# dual_pol_balun_multilayer.net
KiCad netlist of a schematic drawn in EAGLE
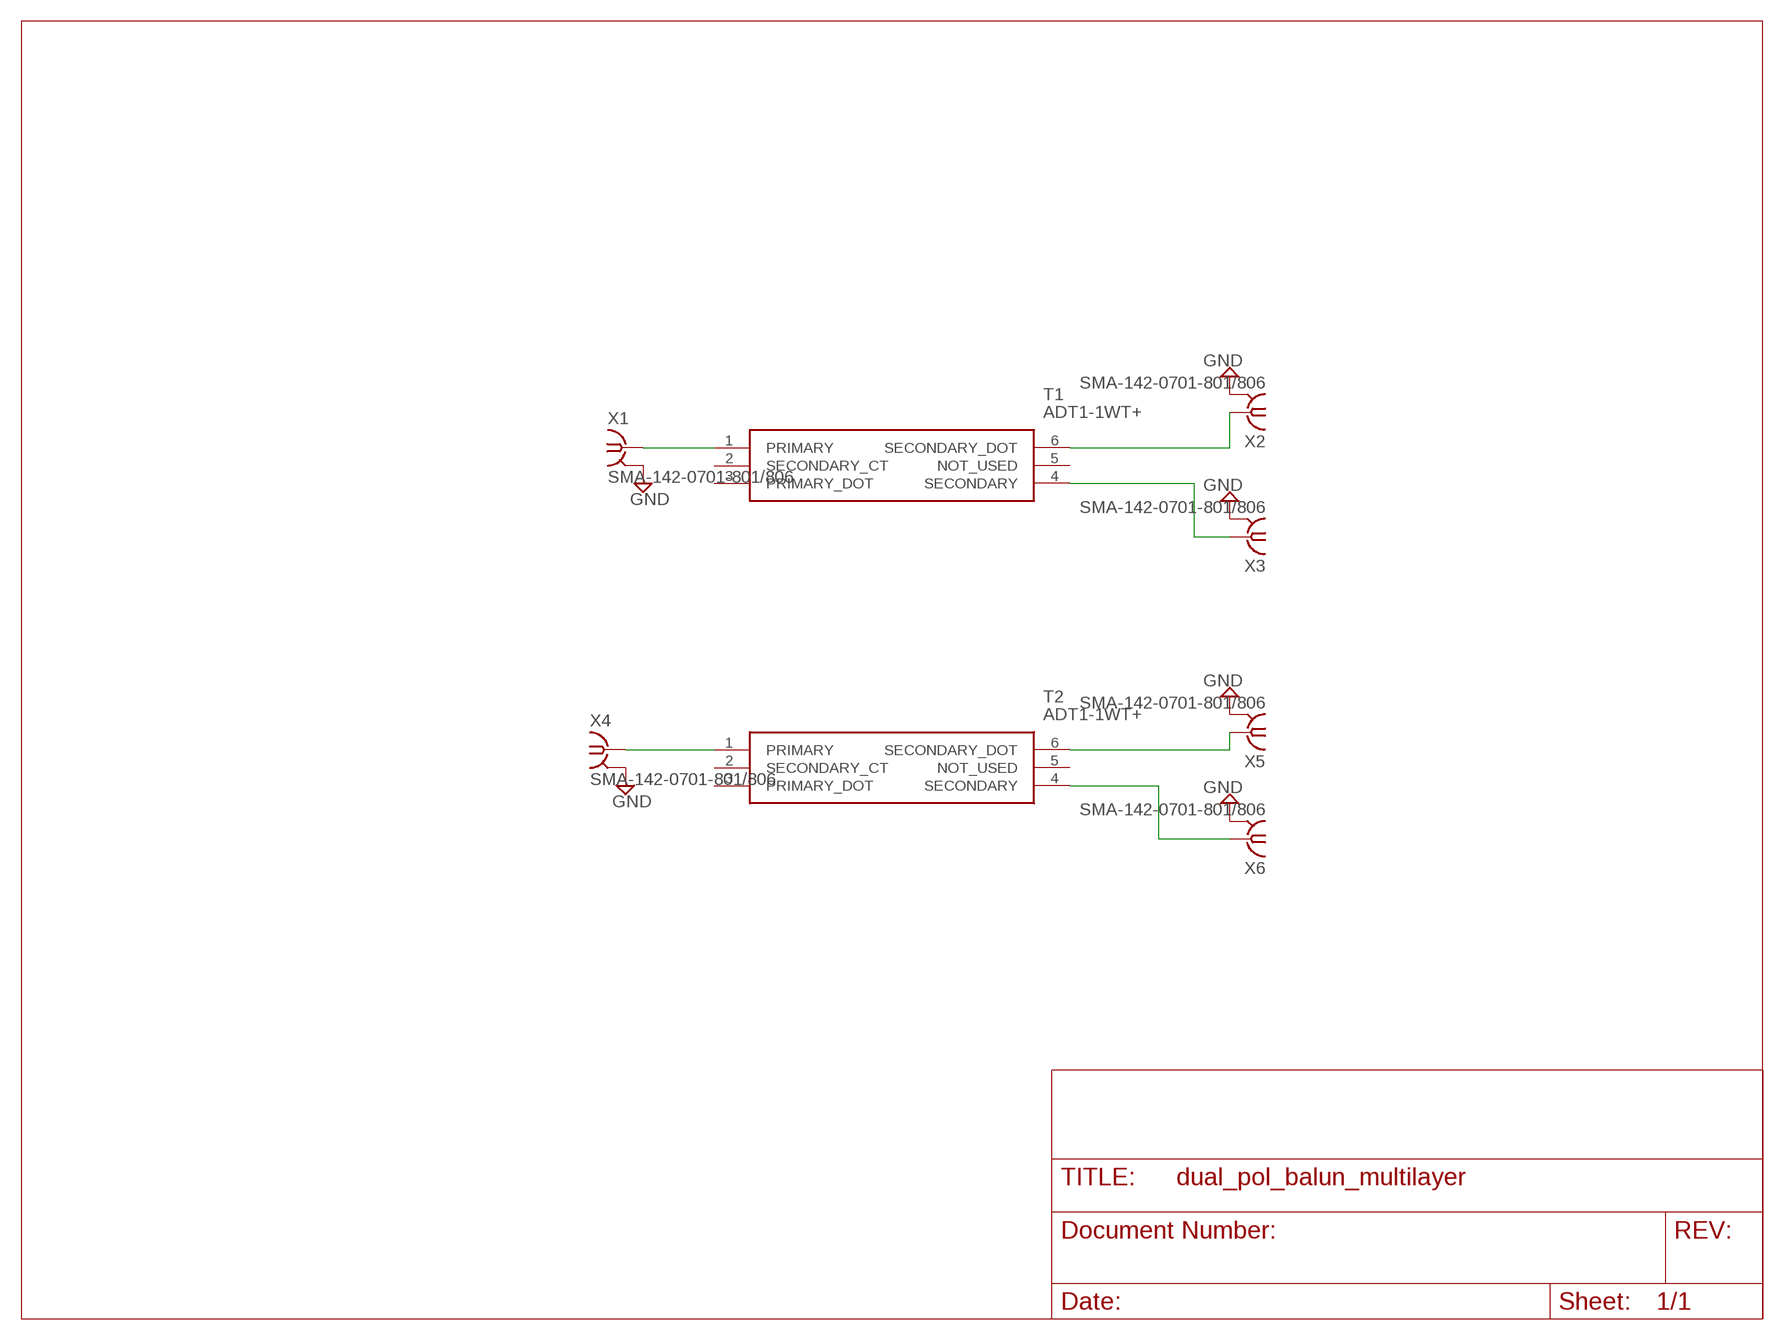
[diagram p0: schematic, sheet 1]

(export (version "E")
  (design (tool "Eeschema 10.0.6"))
  (components
    (comp (ref "T1")
      (value "ADT1-1WT+")
      (footprint "eagle-import:ADT11WT")
      (fields (field (name "MOUSER_PART_NUMBER") "139-ADT1-1WT"))
      (libsource (lib "eagle-import") (part "ADT1-1WT+"))
    )
    (comp (ref "T2")
      (value "ADT1-1WT+")
      (footprint "eagle-import:ADT11WT")
      (fields (field (name "MOUSER_PART_NUMBER") "139-ADT1-1WT"))
      (libsource (lib "eagle-import") (part "ADT1-1WT+"))
    )
    (comp (ref "X1")
      (value "SMA-142-0701-801/806")
      (footprint "eagle-import:J502-ND-142-0701-801_806")
      (fields (field (name "MF") "JOHNSON COMPONENTS") (field (name "MPN") "142-0701-801"))
      (libsource (lib "eagle-import") (part "SMA-142-0701-801/806"))
    )
    (comp (ref "X2")
      (value "SMA-142-0701-801/806")
      (footprint "eagle-import:J502-ND-142-0701-801_806")
      (fields (field (name "MF") "JOHNSON COMPONENTS") (field (name "MPN") "142-0701-801"))
      (libsource (lib "eagle-import") (part "SMA-142-0701-801/806"))
    )
    (comp (ref "X3")
      (value "SMA-142-0701-801/806")
      (footprint "eagle-import:J502-ND-142-0701-801_806")
      (fields (field (name "MF") "JOHNSON COMPONENTS") (field (name "MPN") "142-0701-801"))
      (libsource (lib "eagle-import") (part "SMA-142-0701-801/806"))
    )
    (comp (ref "X4")
      (value "SMA-142-0701-801/806")
      (footprint "eagle-import:J502-ND-142-0701-801_806")
      (fields (field (name "MF") "JOHNSON COMPONENTS") (field (name "MPN") "142-0701-801"))
      (libsource (lib "eagle-import") (part "SMA-142-0701-801/806"))
    )
    (comp (ref "X5")
      (value "SMA-142-0701-801/806")
      (footprint "eagle-import:J502-ND-142-0701-801_806")
      (fields (field (name "MF") "JOHNSON COMPONENTS") (field (name "MPN") "142-0701-801"))
      (libsource (lib "eagle-import") (part "SMA-142-0701-801/806"))
    )
    (comp (ref "X6")
      (value "SMA-142-0701-801/806")
      (footprint "eagle-import:J502-ND-142-0701-801_806")
      (fields (field (name "MF") "JOHNSON COMPONENTS") (field (name "MPN") "142-0701-801"))
      (libsource (lib "eagle-import") (part "SMA-142-0701-801/806"))
    )
  )
  (nets
    (net (code "1") (name "GND") (class "Default")
      (node (ref "X1") (pin "G@1") (pinfunction "2_G@1") (pintype "passive"))
      (node (ref "X1") (pin "G@2") (pinfunction "2_G@2") (pintype "passive"))
      (node (ref "X1") (pin "G@3") (pinfunction "2_G@3") (pintype "passive"))
      (node (ref "X1") (pin "G@4") (pinfunction "2_G@4") (pintype "passive"))
      (node (ref "X2") (pin "G@1") (pinfunction "2_G@1") (pintype "passive"))
      (node (ref "X2") (pin "G@2") (pinfunction "2_G@2") (pintype "passive"))
      (node (ref "X2") (pin "G@3") (pinfunction "2_G@3") (pintype "passive"))
      (node (ref "X2") (pin "G@4") (pinfunction "2_G@4") (pintype "passive"))
      (node (ref "X3") (pin "G@1") (pinfunction "2_G@1") (pintype "passive"))
      (node (ref "X3") (pin "G@2") (pinfunction "2_G@2") (pintype "passive"))
      (node (ref "X3") (pin "G@3") (pinfunction "2_G@3") (pintype "passive"))
      (node (ref "X3") (pin "G@4") (pinfunction "2_G@4") (pintype "passive"))
      (node (ref "X4") (pin "G@1") (pinfunction "2_G@1") (pintype "passive"))
      (node (ref "X4") (pin "G@2") (pinfunction "2_G@2") (pintype "passive"))
      (node (ref "X4") (pin "G@3") (pinfunction "2_G@3") (pintype "passive"))
      (node (ref "X4") (pin "G@4") (pinfunction "2_G@4") (pintype "passive"))
      (node (ref "X5") (pin "G@1") (pinfunction "2_G@1") (pintype "passive"))
      (node (ref "X5") (pin "G@2") (pinfunction "2_G@2") (pintype "passive"))
      (node (ref "X5") (pin "G@3") (pinfunction "2_G@3") (pintype "passive"))
      (node (ref "X5") (pin "G@4") (pinfunction "2_G@4") (pintype "passive"))
      (node (ref "X6") (pin "G@1") (pinfunction "2_G@1") (pintype "passive"))
      (node (ref "X6") (pin "G@2") (pinfunction "2_G@2") (pintype "passive"))
      (node (ref "X6") (pin "G@3") (pinfunction "2_G@3") (pintype "passive"))
      (node (ref "X6") (pin "G@4") (pinfunction "2_G@4") (pintype "passive"))
    )
    (net (code "2") (name "Net-(T1-PRIMARY)") (class "Default")
      (node (ref "T1") (pin "1") (pinfunction "PRIMARY_1") (pintype "bidirectional"))
      (node (ref "X1") (pin "1") (pinfunction "1_1") (pintype "passive"))
    )
    (net (code "3") (name "Net-(T1-SECONDARY)") (class "Default")
      (node (ref "T1") (pin "4") (pinfunction "SECONDARY_4") (pintype "bidirectional"))
      (node (ref "X3") (pin "1") (pinfunction "1_1") (pintype "passive"))
    )
    (net (code "4") (name "Net-(T1-SECONDARY_DOT)") (class "Default")
      (node (ref "T1") (pin "6") (pinfunction "SECONDARY_DOT_6") (pintype "bidirectional"))
      (node (ref "X2") (pin "1") (pinfunction "1_1") (pintype "passive"))
    )
    (net (code "5") (name "Net-(T2-PRIMARY)") (class "Default")
      (node (ref "T2") (pin "1") (pinfunction "PRIMARY_1") (pintype "bidirectional"))
      (node (ref "X4") (pin "1") (pinfunction "1_1") (pintype "passive"))
    )
    (net (code "6") (name "Net-(T2-SECONDARY)") (class "Default")
      (node (ref "T2") (pin "4") (pinfunction "SECONDARY_4") (pintype "bidirectional"))
      (node (ref "X6") (pin "1") (pinfunction "1_1") (pintype "passive"))
    )
    (net (code "7") (name "Net-(T2-SECONDARY_DOT)") (class "Default")
      (node (ref "T2") (pin "6") (pinfunction "SECONDARY_DOT_6") (pintype "bidirectional"))
      (node (ref "X5") (pin "1") (pinfunction "1_1") (pintype "passive"))
    )
    (net (code "8") (name "unconnected-(T1-NOT_USED-Pad5)") (class "Default")
      (node (ref "T1") (pin "5") (pinfunction "NOT_USED_5") (pintype "bidirectional"))
    )
    (net (code "9") (name "unconnected-(T1-PRIMARY_DOT-Pad3)") (class "Default")
      (node (ref "T1") (pin "3") (pinfunction "PRIMARY_DOT_3") (pintype "bidirectional"))
    )
    (net (code "10") (name "unconnected-(T1-SECONDARY_CT-Pad2)") (class "Default")
      (node (ref "T1") (pin "2") (pinfunction "SECONDARY_CT_2") (pintype "bidirectional"))
    )
    (net (code "11") (name "unconnected-(T2-NOT_USED-Pad5)") (class "Default")
      (node (ref "T2") (pin "5") (pinfunction "NOT_USED_5") (pintype "bidirectional"))
    )
    (net (code "12") (name "unconnected-(T2-PRIMARY_DOT-Pad3)") (class "Default")
      (node (ref "T2") (pin "3") (pinfunction "PRIMARY_DOT_3") (pintype "bidirectional"))
    )
    (net (code "13") (name "unconnected-(T2-SECONDARY_CT-Pad2)") (class "Default")
      (node (ref "T2") (pin "2") (pinfunction "SECONDARY_CT_2") (pintype "bidirectional"))
    )
  )
)
